# Breakout.net
KiCad netlist of a schematic drawn in Altium Designer
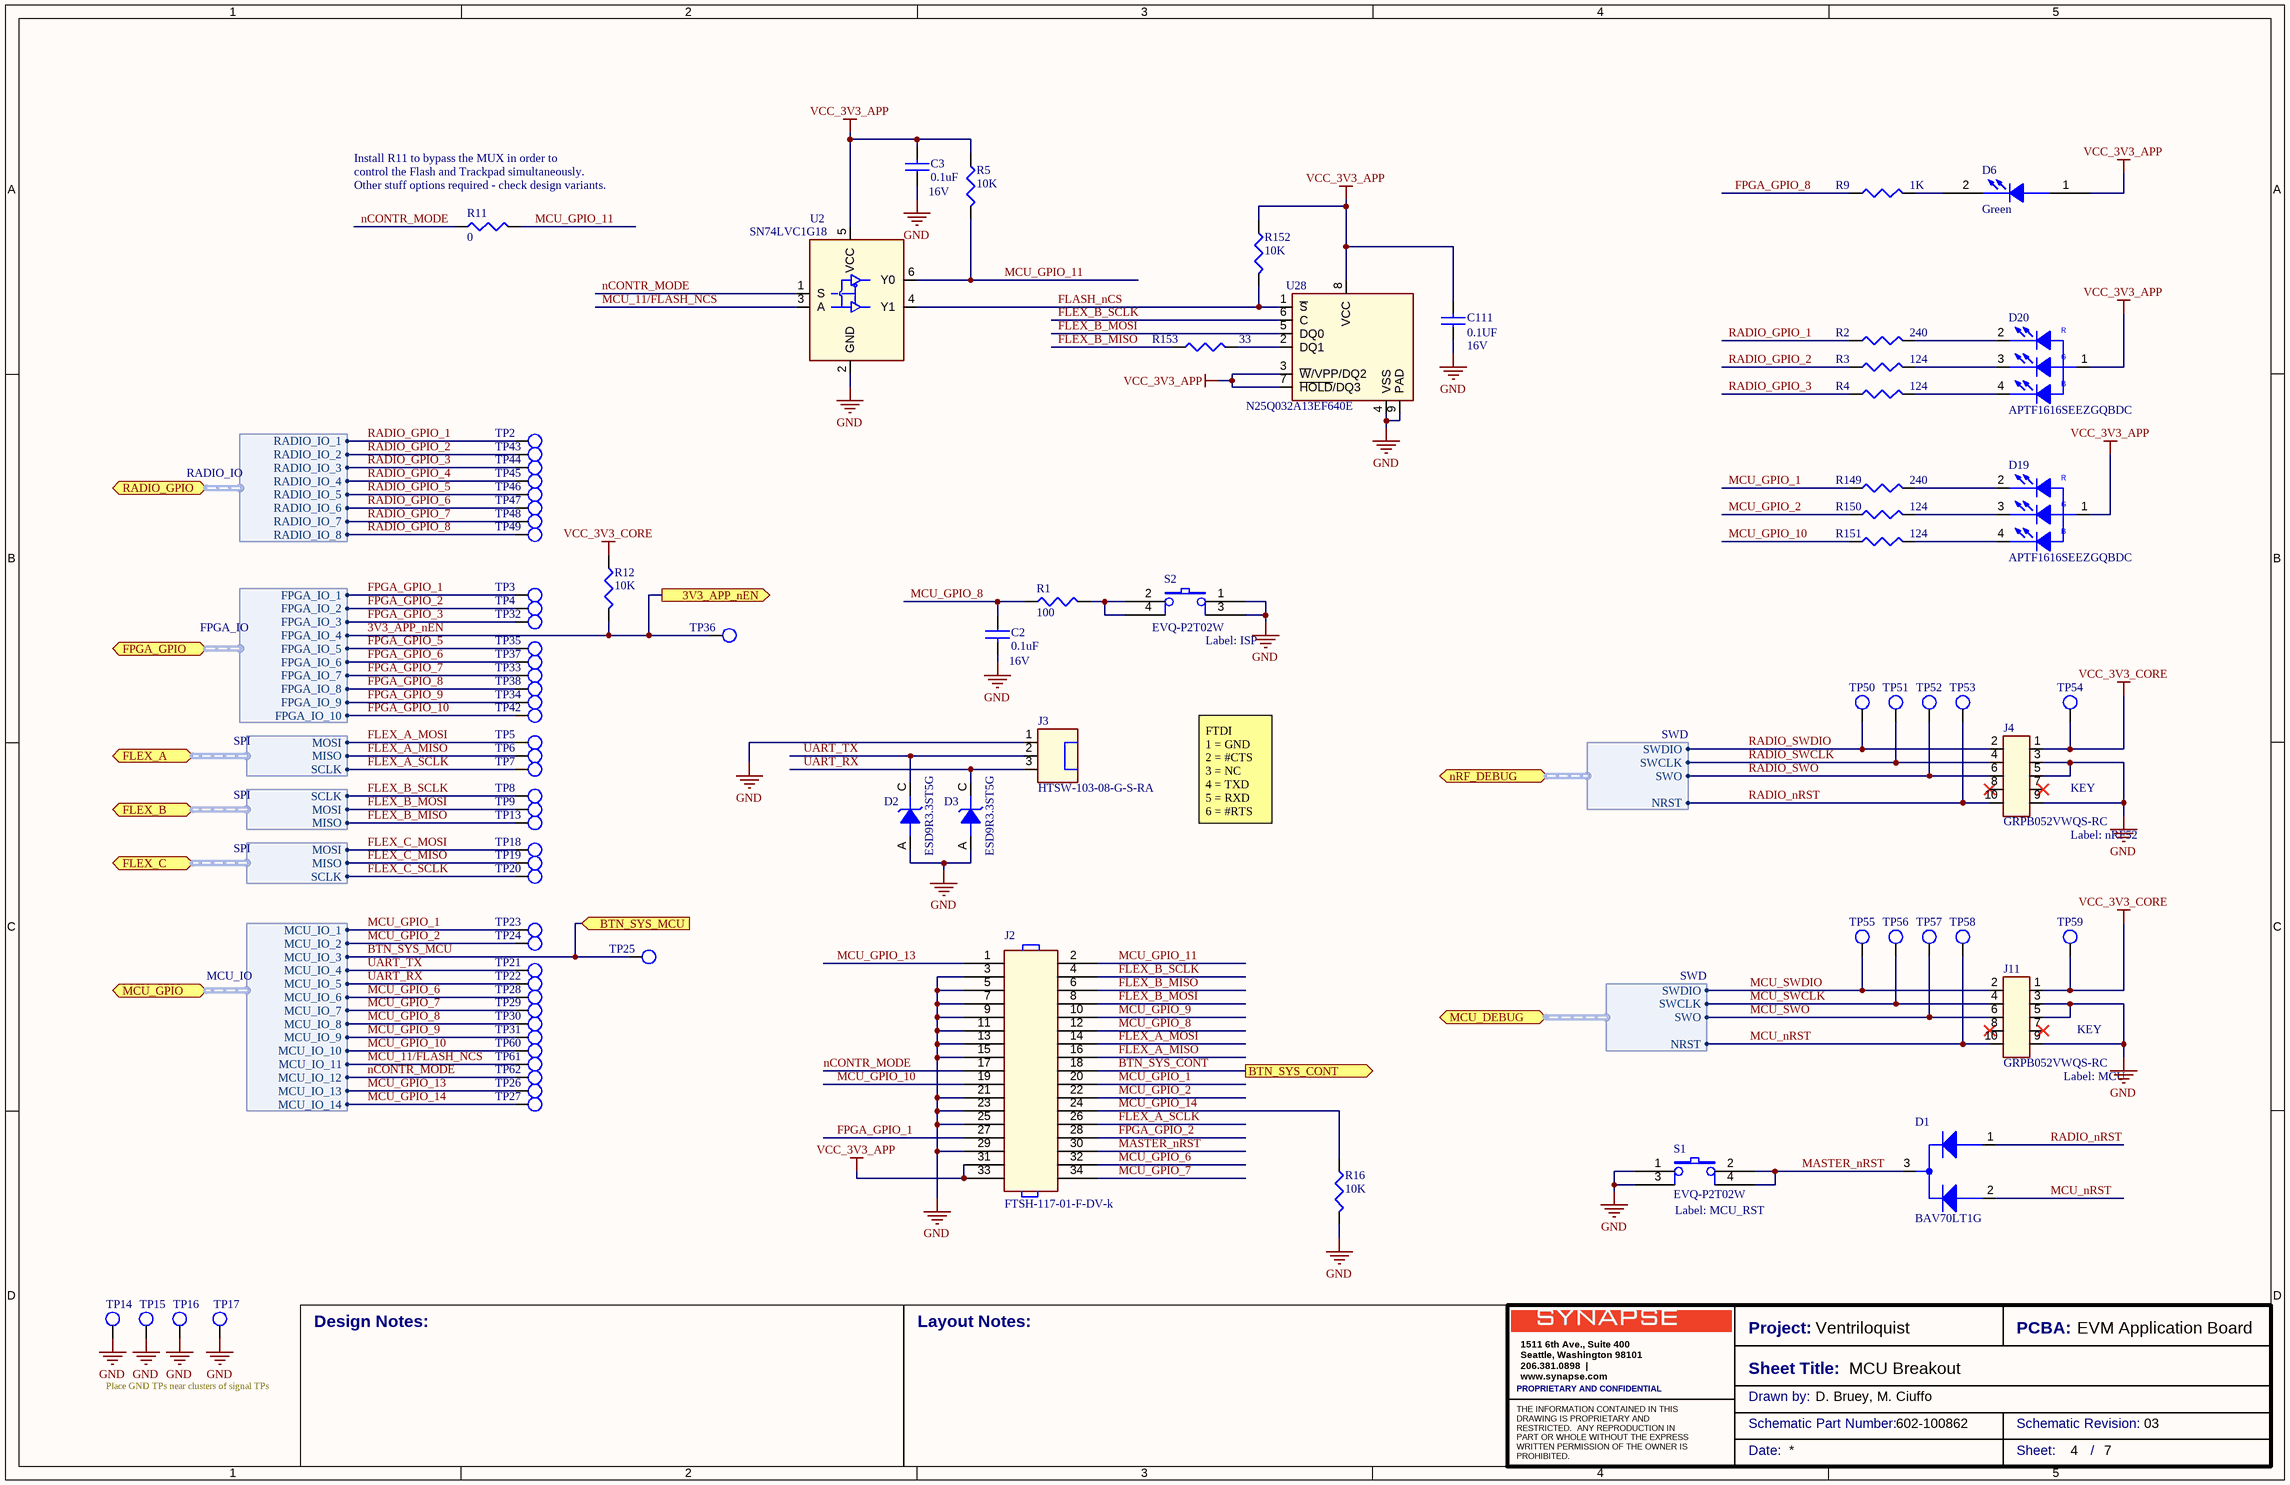
[diagram p0: Breakout.SchDoc]

(export (version "E")
  (design (tool "Eeschema 10.0.6"))
  (components
    (comp (ref "C2")
      (value "0.1uF")
      (footprint "0402-IPCsm_55")
      (description "CAP CER .1UF 16V X7R 0402")
      (fields (field (name "VOLTAGE") "16V") (field (name "MFG") "MURATA") (field (name "TOLERANCE") "10%"))
      (libsource (lib "SynapseLibrary") (part "CAP"))
    )
    (comp (ref "C3")
      (value "0.1uF")
      (footprint "0402-IPCsm_55")
      (description "CAP CER .1UF 16V X7R 0402")
      (fields (field (name "VOLTAGE") "16V") (field (name "MFG") "MURATA") (field (name "TOLERANCE") "10%"))
      (libsource (lib "SynapseLibrary") (part "CAP"))
    )
    (comp (ref "C111")
      (value "0.1UF")
      (footprint "0603-ipcsm_90")
      (description "CAP CER 0.1UF 16V 5% X7R 0603")
      (fields (field (name "VOLTAGE") "16V") (field (name "MFG") "Kemet") (field (name "TOLERANCE") "5%"))
      (libsource (lib "SynapseLibrary") (part "CAP"))
    )
    (comp (ref "D1")
      (value "BAV70LT1G")
      (footprint "SOT23_44H")
      (description "DIODE SWITCH DUAL CC 70V SOT23")
      (fields (field (name "MFG") "ON Semi") (field (name "VOLTAGE") "70V"))
      (libsource (lib "SynapseLibrary") (part "DIODE 2 CC"))
    )
    (comp (ref "D2")
      (value "ESD9R3.3ST5G")
      (footprint "sod923-40")
      (description "TVS DIODE 3.3VWM 7.8VC SOD923")
      (fields (field (name "MFG") "On Semiconductor") (field (name "VOLTAGE") "3.3V"))
      (libsource (lib "SynapseLibrary") (part "TVS_UNI"))
    )
    (comp (ref "D3")
      (value "ESD9R3.3ST5G")
      (footprint "sod923-40")
      (description "TVS DIODE 3.3VWM 7.8VC SOD923")
      (fields (field (name "MFG") "On Semiconductor") (field (name "VOLTAGE") "3.3V"))
      (libsource (lib "SynapseLibrary") (part "TVS_UNI"))
    )
    (comp (ref "D6")
      (value "Green")
      (footprint "led_ltst-c191kgkt_s80")
      (description "LED GREEN CLEAR THIN 0603 SMD")
      (fields (field (name "MFG") "Lite-On Inc") (field (name "VOLTAGE") "3.2V"))
      (libsource (lib "SynapseLibrary") (part "LED"))
    )
    (comp (ref "D19")
      (value "APTF1616SEEZGQBDC")
      (footprint "led_RBG_1p6x1p6_sm")
      (description "LED RGB CLEAR 0606 SMD")
      (fields (field (name "MFG") "Kingbright"))
      (libsource (lib "SynapseLibrary") (part "RGB_CA_HT-B3053FCH"))
    )
    (comp (ref "D20")
      (value "APTF1616SEEZGQBDC")
      (footprint "led_RBG_1p6x1p6_sm")
      (description "LED RGB CLEAR 0606 SMD")
      (fields (field (name "MFG") "Kingbright"))
      (libsource (lib "SynapseLibrary") (part "RGB_CA_HT-B3053FCH"))
    )
    (comp (ref "J2")
      (value "FTSH-117-01-F-DV-k")
      (footprint "FTSH-117-01-XXX-DV-K")
      (description "34 Positions Header, Shrouded Connector 0.050\" (1.27mm) Surface Mount Gold")
      (fields (field (name "MFG") "Samtec"))
      (libsource (lib "SynapseLibrary") (part "HEADER 17X2"))
    )
    (comp (ref "J3")
      (value "HTSW-103-08-G-S-RA")
      (footprint "CON_HDR_1X3_RA")
      (description "3 Positions Header, Unshrouded Connector 0.100\" (2.54mm) Through Hole, Right Angle Gold")
      (fields (field (name "MFG") "Samtec"))
      (libsource (lib "SynapseLibrary") (part "HEADER 3"))
    )
    (comp (ref "J4")
      (value "GRPB052VWQS-RC")
      (footprint "con_hdr_2x5_smt_50l")
      (description "CONN HEADER .050\" 10PS DL SMD AU")
      (fields (field (name "MFG") "Sullins Connector Solutions"))
      (libsource (lib "SynapseLibrary") (part "CONN5x2"))
    )
    (comp (ref "J11")
      (value "GRPB052VWQS-RC")
      (footprint "con_hdr_2x5_smt_50l")
      (description "CONN HEADER .050\" 10PS DL SMD AU")
      (fields (field (name "MFG") "Sullins Connector Solutions"))
      (libsource (lib "SynapseLibrary") (part "CONN5x2"))
    )
    (comp (ref "R1")
      (value "100")
      (footprint "0402-IPCsm_40")
      (description "RES 100 OHM 5% 0402 SMD")
      (fields (field (name "TOLERANCE") "5.00%") (field (name "MFG") "ROHM"))
      (libsource (lib "SynapseLibrary") (part "RES"))
    )
    (comp (ref "R2")
      (value "240")
      (footprint "0402-IPCsm_40")
      (description "RES 240 OHM 1/10W 1% 0402 SMD")
      (fields (field (name "TOLERANCE") "1%") (field (name "MFG") "Panasonic"))
      (libsource (lib "SynapseLibrary") (part "RES"))
    )
    (comp (ref "R3")
      (value "124")
      (footprint "0402-IPCsm_40")
      (description "RES SMD 124 OHM 1% 1/16W 0402")
      (fields (field (name "TOLERANCE") "1.00%") (field (name "MFG") "Yageo"))
      (libsource (lib "SynapseLibrary") (part "RES"))
    )
    (comp (ref "R4")
      (value "124")
      (footprint "0402-IPCsm_40")
      (description "RES SMD 124 OHM 1% 1/16W 0402")
      (fields (field (name "TOLERANCE") "1.00%") (field (name "MFG") "Yageo"))
      (libsource (lib "SynapseLibrary") (part "RES"))
    )
    (comp (ref "R5")
      (value "10K")
      (footprint "0402-IPCsm_40")
      (description "RES 10K OHM 1/10W 5% 0402 SMD")
      (fields (field (name "TOLERANCE") "5%") (field (name "MFG") "Panasonic"))
      (libsource (lib "SynapseLibrary") (part "RES"))
    )
    (comp (ref "R9")
      (value "1K")
      (footprint "0603-IPCsm_56")
      (description "RES 1K 1/10W 1% 0603 SMD")
      (fields (field (name "TOLERANCE") "1.00%") (field (name "VOLTAGE") "50V"))
      (libsource (lib "SynapseLibrary") (part "RES"))
    )
    (comp (ref "R11")
      (value "0")
      (footprint "0402-IPCsm_40")
      (description "RES 0.0 OHM 1/10W JUMP 0402 SMD")
      (fields (field (name "TOLERANCE") "5.00%") (field (name "MFG") "PANASONIC"))
      (libsource (lib "SynapseLibrary") (part "RES"))
    )
    (comp (ref "R12")
      (value "10K")
      (footprint "0402-IPCsm_40")
      (description "RES 10K OHM 1/10W 5% 0402 SMD")
      (fields (field (name "TOLERANCE") "5%") (field (name "MFG") "Panasonic"))
      (libsource (lib "SynapseLibrary") (part "RES"))
    )
    (comp (ref "R16")
      (value "10K")
      (footprint "0402-IPCsm_40")
      (description "RES 10K OHM 1/10W 5% 0402 SMD")
      (fields (field (name "TOLERANCE") "5%") (field (name "MFG") "Panasonic"))
      (libsource (lib "SynapseLibrary") (part "RES"))
    )
    (comp (ref "R149")
      (value "240")
      (footprint "0402-IPCsm_40")
      (description "RES 240 OHM 1/10W 1% 0402 SMD")
      (fields (field (name "TOLERANCE") "1%") (field (name "MFG") "Panasonic"))
      (libsource (lib "SynapseLibrary") (part "RES"))
    )
    (comp (ref "R150")
      (value "124")
      (footprint "0402-IPCsm_40")
      (description "RES SMD 124 OHM 1% 1/16W 0402")
      (fields (field (name "TOLERANCE") "1.00%") (field (name "MFG") "Yageo"))
      (libsource (lib "SynapseLibrary") (part "RES"))
    )
    (comp (ref "R151")
      (value "124")
      (footprint "0402-IPCsm_40")
      (description "RES SMD 124 OHM 1% 1/16W 0402")
      (fields (field (name "TOLERANCE") "1.00%") (field (name "MFG") "Yageo"))
      (libsource (lib "SynapseLibrary") (part "RES"))
    )
    (comp (ref "R152")
      (value "10K")
      (footprint "0402-IPCsm_40")
      (description "RES 10K OHM 1/10W 5% 0402 SMD")
      (fields (field (name "TOLERANCE") "5%") (field (name "MFG") "Panasonic"))
      (libsource (lib "SynapseLibrary") (part "RES"))
    )
    (comp (ref "R153")
      (value "33")
      (footprint "0402-IPCsm_40")
      (description "RES 33 OHM 1/16W 5% 0402 SMD")
      (fields (field (name "TOLERANCE") "5.00%") (field (name "VOLTAGE") "50V"))
      (libsource (lib "SynapseLibrary") (part "RES"))
    )
    (comp (ref "S1")
      (value "EVQ-P2T02W")
      (footprint "SW_EVQP2")
      (description "SWITCH TACTILE SPST-NO 0.02A 15V")
      (fields (field (name "MFG") "Panasonic") (field (name "VOLTAGE") "15VDC"))
      (libsource (lib "SynapseLibrary") (part "EVQ-P2T02W"))
    )
    (comp (ref "S2")
      (value "EVQ-P2T02W")
      (footprint "SW_EVQP2")
      (description "SWITCH TACTILE SPST-NO 0.02A 15V")
      (fields (field (name "MFG") "Panasonic") (field (name "VOLTAGE") "15VDC"))
      (libsource (lib "SynapseLibrary") (part "EVQ-P2T02W"))
    )
    (comp (ref "TP2")
      (value "tp-1mm")
      (footprint "TP-S100_SMT")
      (description "TESTPOINT, 1MM SMD, Square pad, Round SM opening")
      (fields (field (name "MFG") "NA"))
      (libsource (lib "SynapseLibrary") (part "tp_smt"))
    )
    (comp (ref "TP3")
      (value "tp-1mm")
      (footprint "TP-S100_SMT")
      (description "TESTPOINT, 1MM SMD, Square pad, Round SM opening")
      (fields (field (name "MFG") "NA"))
      (libsource (lib "SynapseLibrary") (part "tp_smt"))
    )
    (comp (ref "TP4")
      (value "tp-1mm")
      (footprint "TP-S100_SMT")
      (description "TESTPOINT, 1MM SMD, Square pad, Round SM opening")
      (fields (field (name "MFG") "NA"))
      (libsource (lib "SynapseLibrary") (part "tp_smt"))
    )
    (comp (ref "TP5")
      (value "tp-1mm")
      (footprint "TP-S100_SMT")
      (description "TESTPOINT, 1MM SMD, Square pad, Round SM opening")
      (fields (field (name "MFG") "NA"))
      (libsource (lib "SynapseLibrary") (part "tp_smt"))
    )
    (comp (ref "TP6")
      (value "tp-1mm")
      (footprint "TP-S100_SMT")
      (description "TESTPOINT, 1MM SMD, Square pad, Round SM opening")
      (fields (field (name "MFG") "NA"))
      (libsource (lib "SynapseLibrary") (part "tp_smt"))
    )
    (comp (ref "TP7")
      (value "tp-1mm")
      (footprint "TP-S100_SMT")
      (description "TESTPOINT, 1MM SMD, Square pad, Round SM opening")
      (fields (field (name "MFG") "NA"))
      (libsource (lib "SynapseLibrary") (part "tp_smt"))
    )
    (comp (ref "TP8")
      (value "tp-1mm")
      (footprint "TP-S100_SMT")
      (description "TESTPOINT, 1MM SMD, Square pad, Round SM opening")
      (fields (field (name "MFG") "NA"))
      (libsource (lib "SynapseLibrary") (part "tp_smt"))
    )
    (comp (ref "TP9")
      (value "tp-1mm")
      (footprint "TP-S100_SMT")
      (description "TESTPOINT, 1MM SMD, Square pad, Round SM opening")
      (fields (field (name "MFG") "NA"))
      (libsource (lib "SynapseLibrary") (part "tp_smt"))
    )
    (comp (ref "TP13")
      (value "tp-1mm")
      (footprint "TP-S100_SMT")
      (description "TESTPOINT, 1MM SMD, Square pad, Round SM opening")
      (fields (field (name "MFG") "NA"))
      (libsource (lib "SynapseLibrary") (part "tp_smt"))
    )
    (comp (ref "TP14")
      (value "tp-1mm")
      (footprint "TP-S100_SMT")
      (description "TESTPOINT, 1MM SMD, Square pad, Round SM opening")
      (fields (field (name "MFG") "NA"))
      (libsource (lib "SynapseLibrary") (part "tp_smt"))
    )
    (comp (ref "TP15")
      (value "tp-1mm")
      (footprint "TP-S100_SMT")
      (description "TESTPOINT, 1MM SMD, Square pad, Round SM opening")
      (fields (field (name "MFG") "NA"))
      (libsource (lib "SynapseLibrary") (part "tp_smt"))
    )
    (comp (ref "TP16")
      (value "tp-1mm")
      (footprint "TP-S100_SMT")
      (description "TESTPOINT, 1MM SMD, Square pad, Round SM opening")
      (fields (field (name "MFG") "NA"))
      (libsource (lib "SynapseLibrary") (part "tp_smt"))
    )
    (comp (ref "TP17")
      (value "tp-1mm")
      (footprint "TP-S100_SMT")
      (description "TESTPOINT, 1MM SMD, Square pad, Round SM opening")
      (fields (field (name "MFG") "NA"))
      (libsource (lib "SynapseLibrary") (part "tp_smt"))
    )
    (comp (ref "TP18")
      (value "tp-1mm")
      (footprint "TP-S100_SMT")
      (description "TESTPOINT, 1MM SMD, Square pad, Round SM opening")
      (fields (field (name "MFG") "NA"))
      (libsource (lib "SynapseLibrary") (part "tp_smt"))
    )
    (comp (ref "TP19")
      (value "tp-1mm")
      (footprint "TP-S100_SMT")
      (description "TESTPOINT, 1MM SMD, Square pad, Round SM opening")
      (fields (field (name "MFG") "NA"))
      (libsource (lib "SynapseLibrary") (part "tp_smt"))
    )
    (comp (ref "TP20")
      (value "tp-1mm")
      (footprint "TP-S100_SMT")
      (description "TESTPOINT, 1MM SMD, Square pad, Round SM opening")
      (fields (field (name "MFG") "NA"))
      (libsource (lib "SynapseLibrary") (part "tp_smt"))
    )
    (comp (ref "TP21")
      (value "tp-1mm")
      (footprint "TP-S100_SMT")
      (description "TESTPOINT, 1MM SMD, Square pad, Round SM opening")
      (fields (field (name "MFG") "NA"))
      (libsource (lib "SynapseLibrary") (part "tp_smt"))
    )
    (comp (ref "TP22")
      (value "tp-1mm")
      (footprint "TP-S100_SMT")
      (description "TESTPOINT, 1MM SMD, Square pad, Round SM opening")
      (fields (field (name "MFG") "NA"))
      (libsource (lib "SynapseLibrary") (part "tp_smt"))
    )
    (comp (ref "TP23")
      (value "tp-1mm")
      (footprint "TP-S100_SMT")
      (description "TESTPOINT, 1MM SMD, Square pad, Round SM opening")
      (fields (field (name "MFG") "NA"))
      (libsource (lib "SynapseLibrary") (part "tp_smt"))
    )
    (comp (ref "TP24")
      (value "tp-1mm")
      (footprint "TP-S100_SMT")
      (description "TESTPOINT, 1MM SMD, Square pad, Round SM opening")
      (fields (field (name "MFG") "NA"))
      (libsource (lib "SynapseLibrary") (part "tp_smt"))
    )
    (comp (ref "TP25")
      (value "tp-1mm")
      (footprint "TP-S100_SMT")
      (description "TESTPOINT, 1MM SMD, Square pad, Round SM opening")
      (fields (field (name "MFG") "NA"))
      (libsource (lib "SynapseLibrary") (part "tp_smt"))
    )
    (comp (ref "TP26")
      (value "tp-1mm")
      (footprint "TP-S100_SMT")
      (description "TESTPOINT, 1MM SMD, Square pad, Round SM opening")
      (fields (field (name "MFG") "NA"))
      (libsource (lib "SynapseLibrary") (part "tp_smt"))
    )
    (comp (ref "TP27")
      (value "tp-1mm")
      (footprint "TP-S100_SMT")
      (description "TESTPOINT, 1MM SMD, Square pad, Round SM opening")
      (fields (field (name "MFG") "NA"))
      (libsource (lib "SynapseLibrary") (part "tp_smt"))
    )
    (comp (ref "TP28")
      (value "tp-1mm")
      (footprint "TP-S100_SMT")
      (description "TESTPOINT, 1MM SMD, Square pad, Round SM opening")
      (fields (field (name "MFG") "NA"))
      (libsource (lib "SynapseLibrary") (part "tp_smt"))
    )
    (comp (ref "TP29")
      (value "tp-1mm")
      (footprint "TP-S100_SMT")
      (description "TESTPOINT, 1MM SMD, Square pad, Round SM opening")
      (fields (field (name "MFG") "NA"))
      (libsource (lib "SynapseLibrary") (part "tp_smt"))
    )
    (comp (ref "TP30")
      (value "tp-1mm")
      (footprint "TP-S100_SMT")
      (description "TESTPOINT, 1MM SMD, Square pad, Round SM opening")
      (fields (field (name "MFG") "NA"))
      (libsource (lib "SynapseLibrary") (part "tp_smt"))
    )
    (comp (ref "TP31")
      (value "tp-1mm")
      (footprint "TP-S100_SMT")
      (description "TESTPOINT, 1MM SMD, Square pad, Round SM opening")
      (fields (field (name "MFG") "NA"))
      (libsource (lib "SynapseLibrary") (part "tp_smt"))
    )
    (comp (ref "TP32")
      (value "tp-1mm")
      (footprint "TP-S100_SMT")
      (description "TESTPOINT, 1MM SMD, Square pad, Round SM opening")
      (fields (field (name "MFG") "NA"))
      (libsource (lib "SynapseLibrary") (part "tp_smt"))
    )
    (comp (ref "TP33")
      (value "tp-1mm")
      (footprint "TP-S100_SMT")
      (description "TESTPOINT, 1MM SMD, Square pad, Round SM opening")
      (fields (field (name "MFG") "NA"))
      (libsource (lib "SynapseLibrary") (part "tp_smt"))
    )
    (comp (ref "TP34")
      (value "tp-1mm")
      (footprint "TP-S100_SMT")
      (description "TESTPOINT, 1MM SMD, Square pad, Round SM opening")
      (fields (field (name "MFG") "NA"))
      (libsource (lib "SynapseLibrary") (part "tp_smt"))
    )
    (comp (ref "TP35")
      (value "tp-1mm")
      (footprint "TP-S100_SMT")
      (description "TESTPOINT, 1MM SMD, Square pad, Round SM opening")
      (fields (field (name "MFG") "NA"))
      (libsource (lib "SynapseLibrary") (part "tp_smt"))
    )
    (comp (ref "TP36")
      (value "tp-1mm")
      (footprint "TP-S100_SMT")
      (description "TESTPOINT, 1MM SMD, Square pad, Round SM opening")
      (fields (field (name "MFG") "NA"))
      (libsource (lib "SynapseLibrary") (part "tp_smt"))
    )
    (comp (ref "TP37")
      (value "tp-1mm")
      (footprint "TP-S100_SMT")
      (description "TESTPOINT, 1MM SMD, Square pad, Round SM opening")
      (fields (field (name "MFG") "NA"))
      (libsource (lib "SynapseLibrary") (part "tp_smt"))
    )
    (comp (ref "TP38")
      (value "tp-1mm")
      (footprint "TP-S100_SMT")
      (description "TESTPOINT, 1MM SMD, Square pad, Round SM opening")
      (fields (field (name "MFG") "NA"))
      (libsource (lib "SynapseLibrary") (part "tp_smt"))
    )
    (comp (ref "TP42")
      (value "tp-1mm")
      (footprint "TP-S100_SMT")
      (description "TESTPOINT, 1MM SMD, Square pad, Round SM opening")
      (fields (field (name "MFG") "NA"))
      (libsource (lib "SynapseLibrary") (part "tp_smt"))
    )
    (comp (ref "TP43")
      (value "tp-1mm")
      (footprint "TP-S100_SMT")
      (description "TESTPOINT, 1MM SMD, Square pad, Round SM opening")
      (fields (field (name "MFG") "NA"))
      (libsource (lib "SynapseLibrary") (part "tp_smt"))
    )
    (comp (ref "TP44")
      (value "tp-1mm")
      (footprint "TP-S100_SMT")
      (description "TESTPOINT, 1MM SMD, Square pad, Round SM opening")
      (fields (field (name "MFG") "NA"))
      (libsource (lib "SynapseLibrary") (part "tp_smt"))
    )
    (comp (ref "TP45")
      (value "tp-1mm")
      (footprint "TP-S100_SMT")
      (description "TESTPOINT, 1MM SMD, Square pad, Round SM opening")
      (fields (field (name "MFG") "NA"))
      (libsource (lib "SynapseLibrary") (part "tp_smt"))
    )
    (comp (ref "TP46")
      (value "tp-1mm")
      (footprint "TP-S100_SMT")
      (description "TESTPOINT, 1MM SMD, Square pad, Round SM opening")
      (fields (field (name "MFG") "NA"))
      (libsource (lib "SynapseLibrary") (part "tp_smt"))
    )
    (comp (ref "TP47")
      (value "tp-1mm")
      (footprint "TP-S100_SMT")
      (description "TESTPOINT, 1MM SMD, Square pad, Round SM opening")
      (fields (field (name "MFG") "NA"))
      (libsource (lib "SynapseLibrary") (part "tp_smt"))
    )
    (comp (ref "TP48")
      (value "tp-1mm")
      (footprint "TP-S100_SMT")
      (description "TESTPOINT, 1MM SMD, Square pad, Round SM opening")
      (fields (field (name "MFG") "NA"))
      (libsource (lib "SynapseLibrary") (part "tp_smt"))
    )
    (comp (ref "TP49")
      (value "tp-1mm")
      (footprint "TP-S100_SMT")
      (description "TESTPOINT, 1MM SMD, Square pad, Round SM opening")
      (fields (field (name "MFG") "NA"))
      (libsource (lib "SynapseLibrary") (part "tp_smt"))
    )
    (comp (ref "TP50")
      (value "tp-1mm")
      (footprint "TP-S100_SMT")
      (description "TESTPOINT, 1MM SMD, Square pad, Round SM opening")
      (fields (field (name "MFG") "NA"))
      (libsource (lib "SynapseLibrary") (part "tp_smt"))
    )
    (comp (ref "TP51")
      (value "tp-1mm")
      (footprint "TP-S100_SMT")
      (description "TESTPOINT, 1MM SMD, Square pad, Round SM opening")
      (fields (field (name "MFG") "NA"))
      (libsource (lib "SynapseLibrary") (part "tp_smt"))
    )
    (comp (ref "TP52")
      (value "tp-1mm")
      (footprint "TP-S100_SMT")
      (description "TESTPOINT, 1MM SMD, Square pad, Round SM opening")
      (fields (field (name "MFG") "NA"))
      (libsource (lib "SynapseLibrary") (part "tp_smt"))
    )
    (comp (ref "TP53")
      (value "tp-1mm")
      (footprint "TP-S100_SMT")
      (description "TESTPOINT, 1MM SMD, Square pad, Round SM opening")
      (fields (field (name "MFG") "NA"))
      (libsource (lib "SynapseLibrary") (part "tp_smt"))
    )
    (comp (ref "TP54")
      (value "tp-1mm")
      (footprint "TP-S100_SMT")
      (description "TESTPOINT, 1MM SMD, Square pad, Round SM opening")
      (fields (field (name "MFG") "NA"))
      (libsource (lib "SynapseLibrary") (part "tp_smt"))
    )
    (comp (ref "TP55")
      (value "tp-1mm")
      (footprint "TP-S100_SMT")
      (description "TESTPOINT, 1MM SMD, Square pad, Round SM opening")
      (fields (field (name "MFG") "NA"))
      (libsource (lib "SynapseLibrary") (part "tp_smt"))
    )
    (comp (ref "TP56")
      (value "tp-1mm")
      (footprint "TP-S100_SMT")
      (description "TESTPOINT, 1MM SMD, Square pad, Round SM opening")
      (fields (field (name "MFG") "NA"))
      (libsource (lib "SynapseLibrary") (part "tp_smt"))
    )
    (comp (ref "TP57")
      (value "tp-1mm")
      (footprint "TP-S100_SMT")
      (description "TESTPOINT, 1MM SMD, Square pad, Round SM opening")
      (fields (field (name "MFG") "NA"))
      (libsource (lib "SynapseLibrary") (part "tp_smt"))
    )
    (comp (ref "TP58")
      (value "tp-1mm")
      (footprint "TP-S100_SMT")
      (description "TESTPOINT, 1MM SMD, Square pad, Round SM opening")
      (fields (field (name "MFG") "NA"))
      (libsource (lib "SynapseLibrary") (part "tp_smt"))
    )
    (comp (ref "TP59")
      (value "tp-1mm")
      (footprint "TP-S100_SMT")
      (description "TESTPOINT, 1MM SMD, Square pad, Round SM opening")
      (fields (field (name "MFG") "NA"))
      (libsource (lib "SynapseLibrary") (part "tp_smt"))
    )
    (comp (ref "TP60")
      (value "tp-1mm")
      (footprint "TP-S100_SMT")
      (description "TESTPOINT, 1MM SMD, Square pad, Round SM opening")
      (fields (field (name "MFG") "NA"))
      (libsource (lib "SynapseLibrary") (part "tp_smt"))
    )
    (comp (ref "TP61")
      (value "tp-1mm")
      (footprint "TP-S100_SMT")
      (description "TESTPOINT, 1MM SMD, Square pad, Round SM opening")
      (fields (field (name "MFG") "NA"))
      (libsource (lib "SynapseLibrary") (part "tp_smt"))
    )
    (comp (ref "TP62")
      (value "tp-1mm")
      (footprint "TP-S100_SMT")
      (description "TESTPOINT, 1MM SMD, Square pad, Round SM opening")
      (fields (field (name "MFG") "NA"))
      (libsource (lib "SynapseLibrary") (part "tp_smt"))
    )
    (comp (ref "U2")
      (value "SN74LVC1G18")
      (footprint "SON6_TI_DRY")
      (description "IC SGL OPEN DRAIN BUFFER SC70-5")
      (fields (field (name "MANUFACTURER") "TI"))
      (libsource (lib "SynapseLibrary") (part "SN74LVC1G18DRYR"))
    )
    (comp (ref "U28")
      (value "N25Q032A13EF640E")
      (footprint "MLP8_N25Q032A_F6")
      (description "IC FLASH 32MBIT 108MHZ 8VDFN")
      (fields (field (name "MFG") "Micron"))
      (libsource (lib "SynapseLibrary") (part "N25Q032A13EF640E"))
    )
  )
  (nets
    (net (code "6") (name "/3V3_APP_nEN") (class "Default")
      (node (ref "R12") (pin "2") (pinfunction "2_2") (pintype "passive"))
      (node (ref "TP36") (pin "1") (pinfunction "TP_1") (pintype "passive"))
    )
    (net (code "7") (name "/BTN_SYS_CONT") (class "Default")
      (node (ref "J2") (pin "18") (pinfunction "18_18") (pintype "passive"))
    )
    (net (code "8") (name "/BTN_SYS_MCU") (class "Default")
      (node (ref "TP25") (pin "1") (pinfunction "TP_1") (pintype "passive"))
    )
    (net (code "9") (name "/FLASH_nCS") (class "Default")
      (node (ref "R152") (pin "2") (pinfunction "2_2") (pintype "passive"))
      (node (ref "U2") (pin "4") (pinfunction "Y1_4") (pintype "passive"))
      (node (ref "U28") (pin "1") (pinfunction "~{S}_1") (pintype "passive"))
    )
    (net (code "10") (name "/FLEX_A_MISO") (class "Default")
      (node (ref "J2") (pin "16") (pinfunction "16_16") (pintype "passive"))
      (node (ref "TP6") (pin "1") (pinfunction "TP_1") (pintype "passive"))
    )
    (net (code "11") (name "/FLEX_A_MOSI") (class "Default")
      (node (ref "J2") (pin "14") (pinfunction "14_14") (pintype "passive"))
      (node (ref "TP5") (pin "1") (pinfunction "TP_1") (pintype "passive"))
    )
    (net (code "12") (name "/FLEX_A_SCLK") (class "Default")
      (node (ref "J2") (pin "26") (pinfunction "26_26") (pintype "passive"))
      (node (ref "TP7") (pin "1") (pinfunction "TP_1") (pintype "passive"))
    )
    (net (code "13") (name "/FLEX_B_MISO") (class "Default")
      (node (ref "J2") (pin "6") (pinfunction "6_6") (pintype "passive"))
      (node (ref "R153") (pin "1") (pinfunction "1_1") (pintype "passive"))
      (node (ref "TP13") (pin "1") (pinfunction "TP_1") (pintype "passive"))
    )
    (net (code "14") (name "/FLEX_B_MOSI") (class "Default")
      (node (ref "J2") (pin "8") (pinfunction "8_8") (pintype "passive"))
      (node (ref "TP9") (pin "1") (pinfunction "TP_1") (pintype "passive"))
      (node (ref "U28") (pin "5") (pinfunction "DQ0_5") (pintype "passive"))
    )
    (net (code "15") (name "/FLEX_B_SCLK") (class "Default")
      (node (ref "J2") (pin "4") (pinfunction "4_4") (pintype "passive"))
      (node (ref "TP8") (pin "1") (pinfunction "TP_1") (pintype "passive"))
      (node (ref "U28") (pin "6") (pinfunction "C_6") (pintype "passive"))
    )
    (net (code "16") (name "/FLEX_C_MISO") (class "Default")
      (node (ref "TP19") (pin "1") (pinfunction "TP_1") (pintype "passive"))
    )
    (net (code "17") (name "/FLEX_C_MOSI") (class "Default")
      (node (ref "TP18") (pin "1") (pinfunction "TP_1") (pintype "passive"))
    )
    (net (code "18") (name "/FLEX_C_SCLK") (class "Default")
      (node (ref "TP20") (pin "1") (pinfunction "TP_1") (pintype "passive"))
    )
    (net (code "19") (name "/FPGA_GPIO_1") (class "Default")
      (node (ref "J2") (pin "27") (pinfunction "27_27") (pintype "passive"))
      (node (ref "TP3") (pin "1") (pinfunction "TP_1") (pintype "passive"))
    )
    (net (code "20") (name "/FPGA_GPIO_2") (class "Default")
      (node (ref "J2") (pin "28") (pinfunction "28_28") (pintype "passive"))
      (node (ref "TP4") (pin "1") (pinfunction "TP_1") (pintype "passive"))
    )
    (net (code "21") (name "/FPGA_GPIO_3") (class "Default")
      (node (ref "TP32") (pin "1") (pinfunction "TP_1") (pintype "passive"))
    )
    (net (code "22") (name "/FPGA_GPIO_5") (class "Default")
      (node (ref "TP35") (pin "1") (pinfunction "TP_1") (pintype "passive"))
    )
    (net (code "23") (name "/FPGA_GPIO_6") (class "Default")
      (node (ref "TP37") (pin "1") (pinfunction "TP_1") (pintype "passive"))
    )
    (net (code "24") (name "/FPGA_GPIO_7") (class "Default")
      (node (ref "TP33") (pin "1") (pinfunction "TP_1") (pintype "passive"))
    )
    (net (code "25") (name "/FPGA_GPIO_8") (class "Default")
      (node (ref "R9") (pin "2") (pinfunction "2_2") (pintype "passive"))
      (node (ref "TP38") (pin "1") (pinfunction "TP_1") (pintype "passive"))
    )
    (net (code "26") (name "/FPGA_GPIO_9") (class "Default")
      (node (ref "TP34") (pin "1") (pinfunction "TP_1") (pintype "passive"))
    )
    (net (code "27") (name "/FPGA_GPIO_10") (class "Default")
      (node (ref "TP42") (pin "1") (pinfunction "TP_1") (pintype "passive"))
    )
    (net (code "28") (name "/MASTER_nRST") (class "Default")
      (node (ref "D1") (pin "3") (pinfunction "A_3") (pintype "passive"))
      (node (ref "J2") (pin "30") (pinfunction "30_30") (pintype "passive"))
      (node (ref "S1") (pin "2") (pinfunction "2_2") (pintype "passive"))
      (node (ref "S1") (pin "4") (pinfunction "4_4") (pintype "passive"))
    )
    (net (code "29") (name "/MCU_11{slash}FLASH_NCS") (class "Default")
      (node (ref "TP61") (pin "1") (pinfunction "TP_1") (pintype "passive"))
      (node (ref "U2") (pin "3") (pinfunction "A_3") (pintype "passive"))
    )
    (net (code "30") (name "/MCU_GPIO_1") (class "Default")
      (node (ref "J2") (pin "20") (pinfunction "20_20") (pintype "passive"))
      (node (ref "R149") (pin "1") (pinfunction "1_1") (pintype "passive"))
      (node (ref "TP23") (pin "1") (pinfunction "TP_1") (pintype "passive"))
    )
    (net (code "31") (name "/MCU_GPIO_2") (class "Default")
      (node (ref "J2") (pin "22") (pinfunction "22_22") (pintype "passive"))
      (node (ref "R150") (pin "1") (pinfunction "1_1") (pintype "passive"))
      (node (ref "TP24") (pin "1") (pinfunction "TP_1") (pintype "passive"))
    )
    (net (code "32") (name "/MCU_GPIO_6") (class "Default")
      (node (ref "J2") (pin "32") (pinfunction "32_32") (pintype "passive"))
      (node (ref "TP28") (pin "1") (pinfunction "TP_1") (pintype "passive"))
    )
    (net (code "33") (name "/MCU_GPIO_7") (class "Default")
      (node (ref "J2") (pin "34") (pinfunction "34_34") (pintype "passive"))
      (node (ref "TP29") (pin "1") (pinfunction "TP_1") (pintype "passive"))
    )
    (net (code "34") (name "/MCU_GPIO_8") (class "Default")
      (node (ref "C2") (pin "1") (pinfunction "1_1") (pintype "passive"))
      (node (ref "J2") (pin "12") (pinfunction "12_12") (pintype "passive"))
      (node (ref "R1") (pin "1") (pinfunction "1_1") (pintype "passive"))
      (node (ref "TP30") (pin "1") (pinfunction "TP_1") (pintype "passive"))
    )
    (net (code "35") (name "/MCU_GPIO_9") (class "Default")
      (node (ref "J2") (pin "10") (pinfunction "10_10") (pintype "passive"))
      (node (ref "TP31") (pin "1") (pinfunction "TP_1") (pintype "passive"))
    )
    (net (code "36") (name "/MCU_GPIO_10") (class "Default")
      (node (ref "J2") (pin "19") (pinfunction "19_19") (pintype "passive"))
      (node (ref "R151") (pin "1") (pinfunction "1_1") (pintype "passive"))
      (node (ref "TP60") (pin "1") (pinfunction "TP_1") (pintype "passive"))
    )
    (net (code "37") (name "/MCU_GPIO_11") (class "Default")
      (node (ref "J2") (pin "2") (pinfunction "2_2") (pintype "passive"))
      (node (ref "R11") (pin "2") (pinfunction "2_2") (pintype "passive"))
      (node (ref "R5") (pin "2") (pinfunction "2_2") (pintype "passive"))
      (node (ref "U2") (pin "6") (pinfunction "Y0_6") (pintype "passive"))
    )
    (net (code "38") (name "/MCU_GPIO_13") (class "Default")
      (node (ref "J2") (pin "1") (pinfunction "1_1") (pintype "passive"))
      (node (ref "TP26") (pin "1") (pinfunction "TP_1") (pintype "passive"))
    )
    (net (code "39") (name "/MCU_GPIO_14") (class "Default")
      (node (ref "J2") (pin "24") (pinfunction "24_24") (pintype "passive"))
      (node (ref "R16") (pin "1") (pinfunction "1_1") (pintype "passive"))
      (node (ref "TP27") (pin "1") (pinfunction "TP_1") (pintype "passive"))
    )
    (net (code "40") (name "/MCU_SWCLK") (class "Default")
      (node (ref "J11") (pin "4") (pinfunction "4_4") (pintype "passive"))
      (node (ref "TP56") (pin "1") (pinfunction "TP_1") (pintype "passive"))
    )
    (net (code "41") (name "/MCU_SWDIO") (class "Default")
      (node (ref "J11") (pin "2") (pinfunction "2_2") (pintype "passive"))
      (node (ref "TP55") (pin "1") (pinfunction "TP_1") (pintype "passive"))
    )
    (net (code "42") (name "/MCU_SWO") (class "Default")
      (node (ref "J11") (pin "6") (pinfunction "6_6") (pintype "passive"))
      (node (ref "TP57") (pin "1") (pinfunction "TP_1") (pintype "passive"))
    )
    (net (code "43") (name "/MCU_nRST") (class "Default")
      (node (ref "D1") (pin "2") (pinfunction "C2_2") (pintype "passive"))
      (node (ref "J11") (pin "10") (pinfunction "10_10") (pintype "passive"))
      (node (ref "TP58") (pin "1") (pinfunction "TP_1") (pintype "passive"))
    )
    (net (code "44") (name "/RADIO_GPIO_1") (class "Default")
      (node (ref "R2") (pin "1") (pinfunction "1_1") (pintype "passive"))
      (node (ref "TP2") (pin "1") (pinfunction "TP_1") (pintype "passive"))
    )
    (net (code "45") (name "/RADIO_GPIO_2") (class "Default")
      (node (ref "R3") (pin "1") (pinfunction "1_1") (pintype "passive"))
      (node (ref "TP43") (pin "1") (pinfunction "TP_1") (pintype "passive"))
    )
    (net (code "46") (name "/RADIO_GPIO_3") (class "Default")
      (node (ref "R4") (pin "1") (pinfunction "1_1") (pintype "passive"))
      (node (ref "TP44") (pin "1") (pinfunction "TP_1") (pintype "passive"))
    )
    (net (code "47") (name "/RADIO_GPIO_4") (class "Default")
      (node (ref "TP45") (pin "1") (pinfunction "TP_1") (pintype "passive"))
    )
    (net (code "48") (name "/RADIO_GPIO_5") (class "Default")
      (node (ref "TP46") (pin "1") (pinfunction "TP_1") (pintype "passive"))
    )
    (net (code "49") (name "/RADIO_GPIO_6") (class "Default")
      (node (ref "TP47") (pin "1") (pinfunction "TP_1") (pintype "passive"))
    )
    (net (code "50") (name "/RADIO_GPIO_7") (class "Default")
      (node (ref "TP48") (pin "1") (pinfunction "TP_1") (pintype "passive"))
    )
    (net (code "51") (name "/RADIO_GPIO_8") (class "Default")
      (node (ref "TP49") (pin "1") (pinfunction "TP_1") (pintype "passive"))
    )
    (net (code "52") (name "/RADIO_SWCLK") (class "Default")
      (node (ref "J4") (pin "4") (pinfunction "4_4") (pintype "passive"))
      (node (ref "TP51") (pin "1") (pinfunction "TP_1") (pintype "passive"))
    )
    (net (code "53") (name "/RADIO_SWDIO") (class "Default")
      (node (ref "J4") (pin "2") (pinfunction "2_2") (pintype "passive"))
      (node (ref "TP50") (pin "1") (pinfunction "TP_1") (pintype "passive"))
    )
    (net (code "54") (name "/RADIO_SWO") (class "Default")
      (node (ref "J4") (pin "6") (pinfunction "6_6") (pintype "passive"))
      (node (ref "TP52") (pin "1") (pinfunction "TP_1") (pintype "passive"))
    )
    (net (code "55") (name "/RADIO_nRST") (class "Default")
      (node (ref "D1") (pin "1") (pinfunction "C1_1") (pintype "passive"))
      (node (ref "J4") (pin "10") (pinfunction "10_10") (pintype "passive"))
      (node (ref "TP53") (pin "1") (pinfunction "TP_1") (pintype "passive"))
    )
    (net (code "56") (name "/UART_RX") (class "Default")
      (node (ref "D3") (pin "C") (pinfunction "C_C") (pintype "passive"))
      (node (ref "J3") (pin "3") (pinfunction "3_3") (pintype "passive"))
      (node (ref "TP22") (pin "1") (pinfunction "TP_1") (pintype "passive"))
    )
    (net (code "57") (name "/UART_TX") (class "Default")
      (node (ref "D2") (pin "C") (pinfunction "C_C") (pintype "passive"))
      (node (ref "J3") (pin "2") (pinfunction "2_2") (pintype "passive"))
      (node (ref "TP21") (pin "1") (pinfunction "TP_1") (pintype "passive"))
    )
    (net (code "58") (name "/nCONTR_MODE") (class "Default")
      (node (ref "J2") (pin "17") (pinfunction "17_17") (pintype "passive"))
      (node (ref "R11") (pin "1") (pinfunction "1_1") (pintype "passive"))
      (node (ref "TP62") (pin "1") (pinfunction "TP_1") (pintype "passive"))
      (node (ref "U2") (pin "1") (pinfunction "S_1") (pintype "passive"))
    )
    (net (code "64") (name "GND") (class "Default")
      (node (ref "C111") (pin "1") (pinfunction "1_1") (pintype "passive"))
      (node (ref "C2") (pin "2") (pinfunction "2_2") (pintype "passive"))
      (node (ref "C3") (pin "1") (pinfunction "1_1") (pintype "passive"))
      (node (ref "D2") (pin "A") (pinfunction "A_A") (pintype "passive"))
      (node (ref "D3") (pin "A") (pinfunction "A_A") (pintype "passive"))
      (node (ref "J11") (pin "3") (pinfunction "3_3") (pintype "passive"))
      (node (ref "J11") (pin "5") (pinfunction "5_5") (pintype "passive"))
      (node (ref "J11") (pin "9") (pinfunction "9_9") (pintype "passive"))
      (node (ref "J2") (pin "11") (pinfunction "11_11") (pintype "passive"))
      (node (ref "J2") (pin "13") (pinfunction "13_13") (pintype "passive"))
      (node (ref "J2") (pin "15") (pinfunction "15_15") (pintype "passive"))
      (node (ref "J2") (pin "21") (pinfunction "21_21") (pintype "passive"))
      (node (ref "J2") (pin "23") (pinfunction "23_23") (pintype "passive"))
      (node (ref "J2") (pin "25") (pinfunction "25_25") (pintype "passive"))
      (node (ref "J2") (pin "29") (pinfunction "29_29") (pintype "passive"))
      (node (ref "J2") (pin "3") (pinfunction "3_3") (pintype "passive"))
      (node (ref "J2") (pin "5") (pinfunction "5_5") (pintype "passive"))
      (node (ref "J2") (pin "7") (pinfunction "7_7") (pintype "passive"))
      (node (ref "J2") (pin "9") (pinfunction "9_9") (pintype "passive"))
      (node (ref "J3") (pin "1") (pinfunction "1_1") (pintype "passive"))
      (node (ref "J4") (pin "3") (pinfunction "3_3") (pintype "passive"))
      (node (ref "J4") (pin "5") (pinfunction "5_5") (pintype "passive"))
      (node (ref "J4") (pin "9") (pinfunction "9_9") (pintype "passive"))
      (node (ref "R16") (pin "2") (pinfunction "2_2") (pintype "passive"))
      (node (ref "S1") (pin "1") (pinfunction "1_1") (pintype "passive"))
      (node (ref "S1") (pin "3") (pinfunction "3_3") (pintype "passive"))
      (node (ref "S2") (pin "1") (pinfunction "1_1") (pintype "passive"))
      (node (ref "S2") (pin "3") (pinfunction "3_3") (pintype "passive"))
      (node (ref "TP14") (pin "1") (pinfunction "TP_1") (pintype "passive"))
      (node (ref "TP15") (pin "1") (pinfunction "TP_1") (pintype "passive"))
      (node (ref "TP16") (pin "1") (pinfunction "TP_1") (pintype "passive"))
      (node (ref "TP17") (pin "1") (pinfunction "TP_1") (pintype "passive"))
      (node (ref "U2") (pin "2") (pinfunction "GND_2") (pintype "passive"))
      (node (ref "U28") (pin "4") (pinfunction "VSS_4") (pintype "passive"))
      (node (ref "U28") (pin "9") (pinfunction "PAD_9") (pintype "passive"))
    )
    (net (code "65") (name "Net-(D6-C)") (class "Default")
      (node (ref "D6") (pin "2") (pinfunction "C_2") (pintype "passive"))
      (node (ref "R9") (pin "1") (pinfunction "1_1") (pintype "passive"))
    )
    (net (code "66") (name "Net-(D19-B)") (class "Default")
      (node (ref "D19") (pin "4") (pinfunction "B_4") (pintype "passive"))
      (node (ref "R151") (pin "2") (pinfunction "2_2") (pintype "passive"))
    )
    (net (code "67") (name "Net-(D19-G)") (class "Default")
      (node (ref "D19") (pin "3") (pinfunction "G_3") (pintype "passive"))
      (node (ref "R150") (pin "2") (pinfunction "2_2") (pintype "passive"))
    )
    (net (code "68") (name "Net-(D19-R)") (class "Default")
      (node (ref "D19") (pin "2") (pinfunction "R_2") (pintype "passive"))
      (node (ref "R149") (pin "2") (pinfunction "2_2") (pintype "passive"))
    )
    (net (code "69") (name "Net-(D20-B)") (class "Default")
      (node (ref "D20") (pin "4") (pinfunction "B_4") (pintype "passive"))
      (node (ref "R4") (pin "2") (pinfunction "2_2") (pintype "passive"))
    )
    (net (code "70") (name "Net-(D20-G)") (class "Default")
      (node (ref "D20") (pin "3") (pinfunction "G_3") (pintype "passive"))
      (node (ref "R3") (pin "2") (pinfunction "2_2") (pintype "passive"))
    )
    (net (code "71") (name "Net-(D20-R)") (class "Default")
      (node (ref "D20") (pin "2") (pinfunction "R_2") (pintype "passive"))
      (node (ref "R2") (pin "2") (pinfunction "2_2") (pintype "passive"))
    )
    (net (code "72") (name "Net-(R1-Pad2)") (class "Default")
      (node (ref "R1") (pin "2") (pinfunction "2_2") (pintype "passive"))
      (node (ref "S2") (pin "2") (pinfunction "2_2") (pintype "passive"))
      (node (ref "S2") (pin "4") (pinfunction "4_4") (pintype "passive"))
    )
    (net (code "73") (name "Net-(U28-DQ1)") (class "Default")
      (node (ref "R153") (pin "2") (pinfunction "2_2") (pintype "passive"))
      (node (ref "U28") (pin "2") (pinfunction "DQ1_2") (pintype "passive"))
    )
    (net (code "74") (name "VCC_3V3_APP") (class "Default")
      (node (ref "C111") (pin "2") (pinfunction "2_2") (pintype "passive"))
      (node (ref "C3") (pin "2") (pinfunction "2_2") (pintype "passive"))
      (node (ref "D19") (pin "1") (pinfunction "ANODE_1") (pintype "passive"))
      (node (ref "D20") (pin "1") (pinfunction "ANODE_1") (pintype "passive"))
      (node (ref "D6") (pin "1") (pinfunction "A_1") (pintype "passive"))
      (node (ref "J2") (pin "31") (pinfunction "31_31") (pintype "passive"))
      (node (ref "J2") (pin "33") (pinfunction "33_33") (pintype "passive"))
      (node (ref "R152") (pin "1") (pinfunction "1_1") (pintype "passive"))
      (node (ref "R5") (pin "1") (pinfunction "1_1") (pintype "passive"))
      (node (ref "U2") (pin "5") (pinfunction "VCC_5") (pintype "passive"))
      (node (ref "U28") (pin "3") (pinfunction "~{W}/VPP/DQ2_3") (pintype "passive"))
      (node (ref "U28") (pin "7") (pinfunction "~{HOLD}/DQ3_7") (pintype "passive"))
      (node (ref "U28") (pin "8") (pinfunction "VCC_8") (pintype "passive"))
    )
    (net (code "75") (name "VCC_3V3_CORE") (class "Default")
      (node (ref "J11") (pin "1") (pinfunction "1_1") (pintype "passive"))
      (node (ref "J4") (pin "1") (pinfunction "1_1") (pintype "passive"))
      (node (ref "R12") (pin "1") (pinfunction "1_1") (pintype "passive"))
      (node (ref "TP54") (pin "1") (pinfunction "TP_1") (pintype "passive"))
      (node (ref "TP59") (pin "1") (pinfunction "TP_1") (pintype "passive"))
    )
    (net (code "76") (name "unconnected-(J4-Pad7)") (class "Default")
      (node (ref "J4") (pin "7") (pinfunction "7_7") (pintype "passive+no_connect"))
    )
    (net (code "77") (name "unconnected-(J4-Pad8)") (class "Default")
      (node (ref "J4") (pin "8") (pinfunction "8_8") (pintype "passive+no_connect"))
    )
    (net (code "78") (name "unconnected-(J11-Pad7)") (class "Default")
      (node (ref "J11") (pin "7") (pinfunction "7_7") (pintype "passive+no_connect"))
    )
    (net (code "79") (name "unconnected-(J11-Pad8)") (class "Default")
      (node (ref "J11") (pin "8") (pinfunction "8_8") (pintype "passive+no_connect"))
    )
  )
)
